# Sheet1.net
KiCad netlist of a schematic drawn in Altium Designer
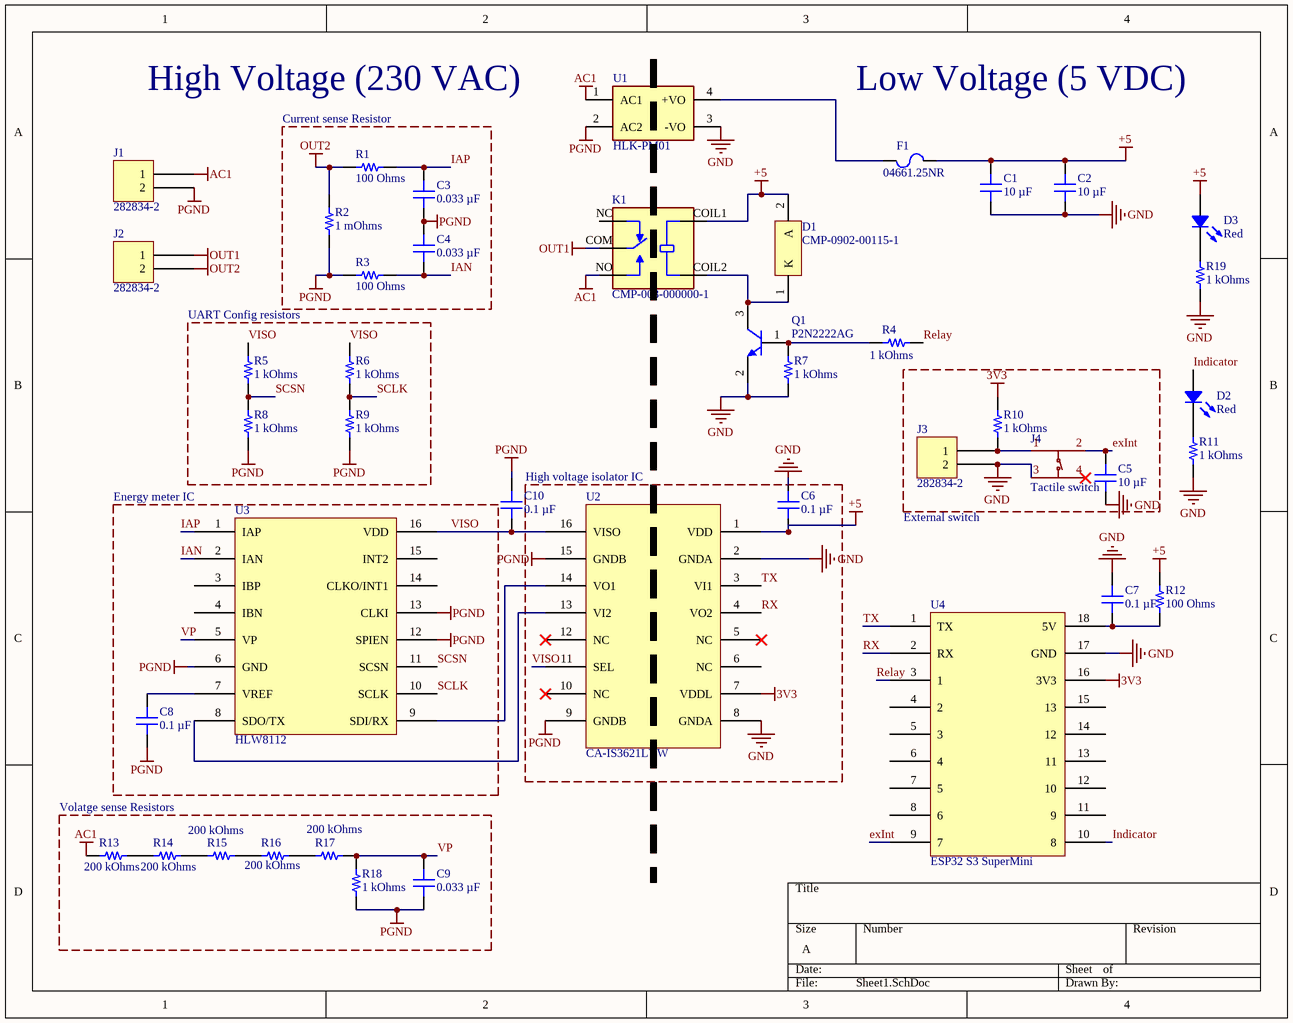
[diagram p0: Sheet1.SchDoc]

(export (version "E")
  (design (tool "Eeschema 10.0.6"))
  (components
    (comp (ref "C1")
      (value "10 µF")
      (footprint "CAP 0805_2012")
      (description "CAP CER 10UF 10V X7S 0805")
      (fields
        (field (name "PART NUMBER") "CL21Y106KPQVPNE")
        (field (name "CAPACITANCE") "10 µF")
        (field (name "MANUFACTURER") "Samsung Electro-Mechanics")
      )
      (libsource (lib "Celestial Altium Library - altium_library") (part "Capacitor"))
    )
    (comp (ref "C2")
      (value "10 µF")
      (footprint "CAP 0805_2012")
      (description "CAP CER 10UF 10V X7S 0805")
      (fields
        (field (name "PART NUMBER") "CL21Y106KPQVPNE")
        (field (name "CAPACITANCE") "10 µF")
        (field (name "MANUFACTURER") "Samsung Electro-Mechanics")
      )
      (libsource (lib "Celestial Altium Library - altium_library") (part "Capacitor"))
    )
    (comp (ref "C3")
      (value "0.033 µF")
      (footprint "CAP 0805_2012")
      (description "CAP CER 0805 33NF 50V X7R 10%")
      (fields
        (field (name "PART NUMBER") "C0805C333K5RECAUTO")
        (field (name "CAPACITANCE") "0.033 µF")
        (field (name "MANUFACTURER") "KEMET")
      )
      (libsource (lib "Celestial Altium Library - altium_library") (part "Capacitor"))
    )
    (comp (ref "C4")
      (value "0.033 µF")
      (footprint "CAP 0805_2012")
      (description "CAP CER 0805 33NF 50V X7R 10%")
      (fields
        (field (name "PART NUMBER") "C0805C333K5RECAUTO")
        (field (name "CAPACITANCE") "0.033 µF")
        (field (name "MANUFACTURER") "KEMET")
      )
      (libsource (lib "Celestial Altium Library - altium_library") (part "Capacitor"))
    )
    (comp (ref "C5")
      (value "10 µF")
      (footprint "CAP 0805_2012")
      (description "CAP CER 10UF 10V X7S 0805")
      (fields
        (field (name "PART NUMBER") "CL21Y106KPQVPNE")
        (field (name "CAPACITANCE") "10 µF")
        (field (name "MANUFACTURER") "Samsung Electro-Mechanics")
      )
      (libsource (lib "Celestial Altium Library - altium_library") (part "Capacitor"))
    )
    (comp (ref "C6")
      (value "0.1 µF")
      (footprint "CAP 0805_2012")
      (description "CAP CER 0.1UF 50V X7R 0805")
      (fields
        (field (name "PART NUMBER") "CC0805MRX7R9BB104")
        (field (name "CAPACITANCE") "0.1 µF")
        (field (name "MANUFACTURER") "Yageo")
      )
      (libsource (lib "Celestial Altium Library - altium_library") (part "Capacitor"))
    )
    (comp (ref "C7")
      (value "0.1 µF")
      (footprint "CAP 0805_2012")
      (description "CAP CER 0.1UF 50V X7R 0805")
      (fields
        (field (name "PART NUMBER") "CC0805MRX7R9BB104")
        (field (name "CAPACITANCE") "0.1 µF")
        (field (name "MANUFACTURER") "Yageo")
      )
      (libsource (lib "Celestial Altium Library - altium_library") (part "Capacitor"))
    )
    (comp (ref "C8")
      (value "0.1 µF")
      (footprint "CAP 0805_2012")
      (description "CAP CER 0.1UF 50V X7R 0805")
      (fields
        (field (name "PART NUMBER") "CC0805MRX7R9BB104")
        (field (name "CAPACITANCE") "0.1 µF")
        (field (name "MANUFACTURER") "Yageo")
      )
      (libsource (lib "Celestial Altium Library - altium_library") (part "Capacitor"))
    )
    (comp (ref "C9")
      (value "0.033 µF")
      (footprint "CAP 0805_2012")
      (description "CAP CER 0805 33NF 50V X7R 10%")
      (fields
        (field (name "PART NUMBER") "C0805C333K5RECAUTO")
        (field (name "CAPACITANCE") "0.033 µF")
        (field (name "MANUFACTURER") "KEMET")
      )
      (libsource (lib "Celestial Altium Library - altium_library") (part "Capacitor"))
    )
    (comp (ref "C10")
      (value "0.1 µF")
      (footprint "CAP 0805_2012")
      (description "CAP CER 0.1UF 50V X7R 0805")
      (fields
        (field (name "PART NUMBER") "CC0805MRX7R9BB104")
        (field (name "CAPACITANCE") "0.1 µF")
        (field (name "MANUFACTURER") "Yageo")
      )
      (libsource (lib "Celestial Altium Library - altium_library") (part "Capacitor"))
    )
    (comp (ref "D1")
      (value "CMP-0902-00115-1")
      (footprint "CMP-0902-00115-1")
      (libsource (lib "Schematic") (part "CMP-0902-00115-1"))
    )
    (comp (ref "D2")
      (value "Red")
      (footprint "LED 0805_2012 RED")
      (description "LED RED 0805 SMD")
      (fields (field (name "PART NUMBER") "5990110007F") (field (name "MANUFACTURER") "Dialight"))
      (libsource (lib "Celestial Altium Library - altium_library") (part "LED"))
    )
    (comp (ref "D3")
      (value "Red")
      (footprint "LED 0805_2012 RED")
      (description "LED RED 0805 SMD")
      (fields (field (name "PART NUMBER") "5990110007F") (field (name "MANUFACTURER") "Dialight"))
      (libsource (lib "Celestial Altium Library - altium_library") (part "LED"))
    )
    (comp (ref "F1")
      (value "04661.25NR")
      (footprint "FUSE 1206_3216 0.6MM")
      (description "FUSE BOARD MOUNT 1.25A 63VAC/VDC")
      (fields (field (name "MANUFACTURER") "Littelfuse Inc."))
      (libsource (lib "Celestial Altium Library - altium_library") (part "MOUNTED FUSE"))
    )
    (comp (ref "J1")
      (value "282834-2")
      (footprint "TE 282834-2")
      (description "TERM BLK 2P SIDE ENT 2.54MM PCB")
      (fields (field (name "MANUFACTURER") "TE Connectivity AMP Connectors") (field (name "VOLTAGE") "150V"))
      (libsource (lib "Celestial Altium Library - altium_library") (part "2 Pin"))
    )
    (comp (ref "J2")
      (value "282834-2")
      (footprint "TE 282834-2")
      (description "TERM BLK 2P SIDE ENT 2.54MM PCB")
      (fields (field (name "MANUFACTURER") "TE Connectivity AMP Connectors") (field (name "VOLTAGE") "150V"))
      (libsource (lib "Celestial Altium Library - altium_library") (part "2 Pin"))
    )
    (comp (ref "J3")
      (value "282834-2")
      (footprint "TE 282834-2")
      (description "TERM BLK 2P SIDE ENT 2.54MM PCB")
      (fields (field (name "MANUFACTURER") "TE Connectivity AMP Connectors") (field (name "VOLTAGE") "150V"))
      (libsource (lib "Celestial Altium Library - altium_library") (part "2 Pin"))
    )
    (comp (ref "J4")
      (value "Tactile switch")
      (footprint "Tactive switch")
      (libsource (lib "Integrated") (part "Tactile switch"))
    )
    (comp (ref "K1")
      (value "CMP-003-000000-1")
      (footprint "CMP-003-000000-1")
      (libsource (lib "Schematic") (part "CMP-003-000000-1"))
    )
    (comp (ref "Q1")
      (value "P2N2222AG")
      (footprint "FP-SOT23-IPC_A")
      (libsource (lib "Schematic") (part "P2N2222AG"))
    )
    (comp (ref "R1")
      (value "100 Ohms")
      (footprint "YAGEO RES 0805_2012")
      (description "RES 100 OHM 1% 1/8W 0805")
      (fields (field (name "PART NUMBER") "RC0805FR-07100RL") (field (name "MANUFACTURER") "Yageo"))
      (libsource (lib "Celestial Altium Library - altium_library") (part "Resistor"))
    )
    (comp (ref "R2")
      (value "1 mOhms")
      (footprint "RES 1206_3216")
      (description "RES 0.001 OHM 1% 1W 1206")
      (fields (field (name "PART NUMBER") "CRK0612-FZ-R001E") (field (name "MANUFACTURER") "Bourns Inc."))
      (libsource (lib "Celestial Altium Library - altium_library") (part "Resistor"))
    )
    (comp (ref "R3")
      (value "100 Ohms")
      (footprint "YAGEO RES 0805_2012")
      (description "RES 100 OHM 1% 1/8W 0805")
      (fields (field (name "PART NUMBER") "RC0805FR-07100RL") (field (name "MANUFACTURER") "Yageo"))
      (libsource (lib "Celestial Altium Library - altium_library") (part "Resistor"))
    )
    (comp (ref "R4")
      (value "1 kOhms")
      (footprint "RES 0805_2012")
      (description "RES SMD 1K OHM 0.1% 1/4W 0805")
      (fields
        (field (name "PART NUMBER") "1-2176092-8")
        (field (name "MANUFACTURER") "TE Connectivity Passive Product")
      )
      (libsource (lib "Celestial Altium Library - altium_library") (part "Resistor"))
    )
    (comp (ref "R5")
      (value "1 kOhms")
      (footprint "RES 0805_2012")
      (description "RES SMD 1K OHM 0.1% 1/4W 0805")
      (fields
        (field (name "PART NUMBER") "1-2176092-8")
        (field (name "MANUFACTURER") "TE Connectivity Passive Product")
      )
      (libsource (lib "Celestial Altium Library - altium_library") (part "Resistor"))
    )
    (comp (ref "R6")
      (value "1 kOhms")
      (footprint "RES 0805_2012")
      (description "RES SMD 1K OHM 0.1% 1/4W 0805")
      (fields
        (field (name "PART NUMBER") "1-2176092-8")
        (field (name "MANUFACTURER") "TE Connectivity Passive Product")
      )
      (libsource (lib "Celestial Altium Library - altium_library") (part "Resistor"))
    )
    (comp (ref "R7")
      (value "1 kOhms")
      (footprint "RES 0805_2012")
      (description "RES SMD 1K OHM 0.1% 1/4W 0805")
      (fields
        (field (name "PART NUMBER") "1-2176092-8")
        (field (name "MANUFACTURER") "TE Connectivity Passive Product")
      )
      (libsource (lib "Celestial Altium Library - altium_library") (part "Resistor"))
    )
    (comp (ref "R8")
      (value "1 kOhms")
      (footprint "RES 0805_2012")
      (description "RES SMD 1K OHM 0.1% 1/4W 0805")
      (fields
        (field (name "PART NUMBER") "1-2176092-8")
        (field (name "MANUFACTURER") "TE Connectivity Passive Product")
      )
      (libsource (lib "Celestial Altium Library - altium_library") (part "Resistor"))
    )
    (comp (ref "R9")
      (value "1 kOhms")
      (footprint "RES 0805_2012")
      (description "RES SMD 1K OHM 0.1% 1/4W 0805")
      (fields
        (field (name "PART NUMBER") "1-2176092-8")
        (field (name "MANUFACTURER") "TE Connectivity Passive Product")
      )
      (libsource (lib "Celestial Altium Library - altium_library") (part "Resistor"))
    )
    (comp (ref "R10")
      (value "1 kOhms")
      (footprint "RES 0805_2012")
      (description "RES SMD 1K OHM 0.1% 1/4W 0805")
      (fields
        (field (name "PART NUMBER") "1-2176092-8")
        (field (name "MANUFACTURER") "TE Connectivity Passive Product")
      )
      (libsource (lib "Celestial Altium Library - altium_library") (part "Resistor"))
    )
    (comp (ref "R11")
      (value "1 kOhms")
      (footprint "RES 0805_2012")
      (description "RES SMD 1K OHM 0.1% 1/4W 0805")
      (fields
        (field (name "PART NUMBER") "1-2176092-8")
        (field (name "MANUFACTURER") "TE Connectivity Passive Product")
      )
      (libsource (lib "Celestial Altium Library - altium_library") (part "Resistor"))
    )
    (comp (ref "R12")
      (value "100 Ohms")
      (footprint "YAGEO RES 0805_2012")
      (description "RES 100 OHM 1% 1/8W 0805")
      (fields (field (name "PART NUMBER") "RC0805FR-07100RL") (field (name "MANUFACTURER") "Yageo"))
      (libsource (lib "Celestial Altium Library - altium_library") (part "Resistor"))
    )
    (comp (ref "R13")
      (value "200 kOhms")
      (footprint "RES 2512_6432")
      (description "RES 200K OHM 1% 1W 2512")
      (fields
        (field (name "PART NUMBER") "RMCF2512FT200K")
        (field (name "MANUFACTURER") "Stackpole Electronics Inc")
      )
      (libsource (lib "Celestial Altium Library - altium_library") (part "Resistor"))
    )
    (comp (ref "R14")
      (value "200 kOhms")
      (footprint "RES 2512_6432")
      (description "RES 200K OHM 1% 1W 2512")
      (fields
        (field (name "PART NUMBER") "RMCF2512FT200K")
        (field (name "MANUFACTURER") "Stackpole Electronics Inc")
      )
      (libsource (lib "Celestial Altium Library - altium_library") (part "Resistor"))
    )
    (comp (ref "R15")
      (value "200 kOhms")
      (footprint "RES 2512_6432")
      (description "RES 200K OHM 1% 1W 2512")
      (fields
        (field (name "PART NUMBER") "RMCF2512FT200K")
        (field (name "MANUFACTURER") "Stackpole Electronics Inc")
      )
      (libsource (lib "Celestial Altium Library - altium_library") (part "Resistor"))
    )
    (comp (ref "R16")
      (value "200 kOhms")
      (footprint "RES 2512_6432")
      (description "RES 200K OHM 1% 1W 2512")
      (fields
        (field (name "PART NUMBER") "RMCF2512FT200K")
        (field (name "MANUFACTURER") "Stackpole Electronics Inc")
      )
      (libsource (lib "Celestial Altium Library - altium_library") (part "Resistor"))
    )
    (comp (ref "R17")
      (value "200 kOhms")
      (footprint "RES 2512_6432")
      (description "RES 200K OHM 1% 1W 2512")
      (fields
        (field (name "PART NUMBER") "RMCF2512FT200K")
        (field (name "MANUFACTURER") "Stackpole Electronics Inc")
      )
      (libsource (lib "Celestial Altium Library - altium_library") (part "Resistor"))
    )
    (comp (ref "R18")
      (value "1 kOhms")
      (footprint "RES 0805_2012")
      (description "RES SMD 1K OHM 0.1% 1/4W 0805")
      (fields
        (field (name "PART NUMBER") "1-2176092-8")
        (field (name "MANUFACTURER") "TE Connectivity Passive Product")
      )
      (libsource (lib "Celestial Altium Library - altium_library") (part "Resistor"))
    )
    (comp (ref "R19")
      (value "1 kOhms")
      (footprint "RES 0805_2012")
      (description "RES SMD 1K OHM 0.1% 1/4W 0805")
      (fields
        (field (name "PART NUMBER") "1-2176092-8")
        (field (name "MANUFACTURER") "TE Connectivity Passive Product")
      )
      (libsource (lib "Celestial Altium Library - altium_library") (part "Resistor"))
    )
    (comp (ref "U1")
      (value "HLK-PM01")
      (footprint "HLK-PM01")
      (libsource (lib "Schematic") (part "HLK-PM01"))
    )
    (comp (ref "U2")
      (value "CA-IS3621LVW")
      (footprint "CA-IS3621LVW")
      (libsource (lib "Integrated") (part "CA-IS3621LVW"))
    )
    (comp (ref "U3") (value "HLW8112") (footprint "HLW8112") (libsource (lib "Schematic") (part "HLW8112")))
    (comp (ref "U4")
      (value "ESP32 S3 SuperMini")
      (footprint "ESP32 S3 SuperMini")
      (libsource (lib "Schematic") (part "ESP32 S3 SuperMini"))
    )
  )
  (nets
    (net (code "1") (name "+5") (class "Default")
      (node (ref "C1") (pin "1") (pinfunction "1_1") (pintype "passive"))
      (node (ref "C2") (pin "1") (pinfunction "1_1") (pintype "passive"))
      (node (ref "C6") (pin "1") (pinfunction "1_1") (pintype "passive"))
      (node (ref "D1") (pin "2") (pinfunction "A_2") (pintype "passive"))
      (node (ref "D3") (pin "1") (pinfunction "1_1") (pintype "passive"))
      (node (ref "F1") (pin "2") (pintype "passive"))
      (node (ref "K1") (pin "COIL1") (pinfunction "COIL1_COIL1") (pintype "passive"))
      (node (ref "R12") (pin "2") (pinfunction "2_2") (pintype "passive"))
      (node (ref "U2") (pin "1") (pinfunction "VDD_1") (pintype "passive"))
    )
    (net (code "2") (name "/IAN") (class "Default")
      (node (ref "C4") (pin "1") (pinfunction "1_1") (pintype "passive"))
      (node (ref "R3") (pin "2") (pinfunction "2_2") (pintype "passive"))
      (node (ref "U3") (pin "2") (pinfunction "IAN_2") (pintype "passive"))
    )
    (net (code "3") (name "/IAP") (class "Default")
      (node (ref "C3") (pin "2") (pinfunction "2_2") (pintype "passive"))
      (node (ref "R1") (pin "2") (pinfunction "2_2") (pintype "passive"))
      (node (ref "U3") (pin "1") (pinfunction "IAP_1") (pintype "passive"))
    )
    (net (code "4") (name "/Indicator") (class "Default")
      (node (ref "D2") (pin "1") (pinfunction "1_1") (pintype "passive"))
      (node (ref "U4") (pin "10") (pinfunction "8_10") (pintype "passive"))
    )
    (net (code "5") (name "/RX") (class "Default")
      (node (ref "U2") (pin "4") (pinfunction "VO2_4") (pintype "passive"))
      (node (ref "U4") (pin "2") (pinfunction "RX_2") (pintype "passive"))
    )
    (net (code "6") (name "/Relay") (class "Default")
      (node (ref "R4") (pin "2") (pinfunction "2_2") (pintype "passive"))
      (node (ref "U4") (pin "3") (pinfunction "1_3") (pintype "passive"))
    )
    (net (code "7") (name "/SCLK") (class "Default")
      (node (ref "R6") (pin "1") (pinfunction "1_1") (pintype "passive"))
      (node (ref "R9") (pin "2") (pinfunction "2_2") (pintype "passive"))
      (node (ref "U3") (pin "10") (pinfunction "SCLK_10") (pintype "passive"))
    )
    (net (code "8") (name "/SCSN") (class "Default")
      (node (ref "R5") (pin "1") (pinfunction "1_1") (pintype "passive"))
      (node (ref "R8") (pin "2") (pinfunction "2_2") (pintype "passive"))
      (node (ref "U3") (pin "11") (pinfunction "SCSN_11") (pintype "passive"))
    )
    (net (code "9") (name "/TX") (class "Default")
      (node (ref "U2") (pin "3") (pinfunction "VI1_3") (pintype "passive"))
      (node (ref "U4") (pin "1") (pinfunction "TX_1") (pintype "passive"))
    )
    (net (code "10") (name "/VISO") (class "Default")
      (node (ref "C10") (pin "1") (pinfunction "1_1") (pintype "passive"))
      (node (ref "R5") (pin "2") (pinfunction "2_2") (pintype "passive"))
      (node (ref "R6") (pin "2") (pinfunction "2_2") (pintype "passive"))
      (node (ref "U2") (pin "11") (pinfunction "SEL_11") (pintype "passive"))
      (node (ref "U2") (pin "16") (pinfunction "VISO_16") (pintype "passive"))
      (node (ref "U3") (pin "16") (pinfunction "VDD_16") (pintype "passive"))
    )
    (net (code "11") (name "/VP") (class "Default")
      (node (ref "C9") (pin "2") (pinfunction "2_2") (pintype "passive"))
      (node (ref "R17") (pin "2") (pinfunction "2_2") (pintype "passive"))
      (node (ref "R18") (pin "2") (pinfunction "2_2") (pintype "passive"))
      (node (ref "U3") (pin "5") (pinfunction "VP_5") (pintype "passive"))
    )
    (net (code "12") (name "/exInt") (class "Default")
      (node (ref "C5") (pin "1") (pinfunction "1_1") (pintype "passive"))
      (node (ref "J4") (pin "2") (pinfunction "B_2") (pintype "passive"))
      (node (ref "U4") (pin "9") (pinfunction "7_9") (pintype "passive"))
    )
    (net (code "13") (name "3V3") (class "Default")
      (node (ref "R10") (pin "1") (pinfunction "1_1") (pintype "passive"))
      (node (ref "U2") (pin "7") (pinfunction "VDDL_7") (pintype "passive"))
      (node (ref "U4") (pin "16") (pinfunction "3V3_16") (pintype "passive"))
    )
    (net (code "14") (name "AC1") (class "Default")
      (node (ref "J1") (pin "1") (pinfunction "1_1") (pintype "passive"))
      (node (ref "K1") (pin "NO") (pinfunction "NO_NO") (pintype "passive"))
      (node (ref "R13") (pin "1") (pinfunction "1_1") (pintype "passive"))
      (node (ref "U1") (pin "1") (pinfunction "AC1_1") (pintype "passive"))
    )
    (net (code "15") (name "GND") (class "Default")
      (node (ref "C1") (pin "2") (pinfunction "2_2") (pintype "passive"))
      (node (ref "C2") (pin "2") (pinfunction "2_2") (pintype "passive"))
      (node (ref "C5") (pin "2") (pinfunction "2_2") (pintype "passive"))
      (node (ref "C6") (pin "2") (pinfunction "2_2") (pintype "passive"))
      (node (ref "C7") (pin "2") (pinfunction "2_2") (pintype "passive"))
      (node (ref "J3") (pin "2") (pinfunction "2_2") (pintype "passive"))
      (node (ref "J4") (pin "3") (pinfunction "C_3") (pintype "passive"))
      (node (ref "Q1") (pin "2") (pinfunction "E_2") (pintype "passive"))
      (node (ref "R11") (pin "2") (pinfunction "2_2") (pintype "passive"))
      (node (ref "R19") (pin "2") (pinfunction "2_2") (pintype "passive"))
      (node (ref "R7") (pin "1") (pinfunction "1_1") (pintype "passive"))
      (node (ref "U1") (pin "3") (pinfunction "-VO_3") (pintype "passive"))
      (node (ref "U2") (pin "2") (pinfunction "GNDA_2") (pintype "passive"))
      (node (ref "U2") (pin "8") (pinfunction "GNDA_8") (pintype "passive"))
      (node (ref "U4") (pin "17") (pinfunction "GND_17") (pintype "passive"))
    )
    (net (code "16") (name "Net-(D1-K)") (class "Default")
      (node (ref "D1") (pin "1") (pinfunction "K_1") (pintype "passive"))
      (node (ref "K1") (pin "COIL2") (pinfunction "COIL2_COIL2") (pintype "passive"))
      (node (ref "Q1") (pin "3") (pinfunction "C_3") (pintype "passive"))
    )
    (net (code "17") (name "Net-(D2-Pad2)") (class "Default")
      (node (ref "D2") (pin "2") (pinfunction "2_2") (pintype "passive"))
      (node (ref "R11") (pin "1") (pinfunction "1_1") (pintype "passive"))
    )
    (net (code "18") (name "Net-(D3-Pad2)") (class "Default")
      (node (ref "D3") (pin "2") (pinfunction "2_2") (pintype "passive"))
      (node (ref "R19") (pin "1") (pinfunction "1_1") (pintype "passive"))
    )
    (net (code "19") (name "Net-(J4-A)") (class "Default")
      (node (ref "J3") (pin "1") (pinfunction "1_1") (pintype "passive"))
      (node (ref "J4") (pin "1") (pinfunction "A_1") (pintype "passive"))
      (node (ref "R10") (pin "2") (pinfunction "2_2") (pintype "passive"))
    )
    (net (code "20") (name "Net-(Q1-B)") (class "Default")
      (node (ref "Q1") (pin "1") (pinfunction "B_1") (pintype "passive"))
      (node (ref "R4") (pin "1") (pinfunction "1_1") (pintype "passive"))
      (node (ref "R7") (pin "2") (pinfunction "2_2") (pintype "passive"))
    )
    (net (code "21") (name "Net-(R13-Pad2)") (class "Default")
      (node (ref "R13") (pin "2") (pinfunction "2_2") (pintype "passive"))
      (node (ref "R14") (pin "1") (pinfunction "1_1") (pintype "passive"))
    )
    (net (code "22") (name "Net-(R14-Pad2)") (class "Default")
      (node (ref "R14") (pin "2") (pinfunction "2_2") (pintype "passive"))
      (node (ref "R15") (pin "1") (pinfunction "1_1") (pintype "passive"))
    )
    (net (code "23") (name "Net-(R15-Pad2)") (class "Default")
      (node (ref "R15") (pin "2") (pinfunction "2_2") (pintype "passive"))
      (node (ref "R16") (pin "1") (pinfunction "1_1") (pintype "passive"))
    )
    (net (code "24") (name "Net-(R16-Pad2)") (class "Default")
      (node (ref "R16") (pin "2") (pinfunction "2_2") (pintype "passive"))
      (node (ref "R17") (pin "1") (pinfunction "1_1") (pintype "passive"))
    )
    (net (code "25") (name "Net-(U1-+VO)") (class "Default")
      (node (ref "F1") (pin "1") (pintype "passive"))
      (node (ref "U1") (pin "4") (pinfunction "+VO_4") (pintype "passive"))
    )
    (net (code "26") (name "Net-(U2-VI2)") (class "Default")
      (node (ref "U2") (pin "13") (pinfunction "VI2_13") (pintype "passive"))
      (node (ref "U3") (pin "8") (pinfunction "SDO/TX_8") (pintype "passive"))
    )
    (net (code "27") (name "Net-(U2-VO1)") (class "Default")
      (node (ref "U2") (pin "14") (pinfunction "VO1_14") (pintype "passive"))
      (node (ref "U3") (pin "9") (pinfunction "SDI/RX_9") (pintype "passive"))
    )
    (net (code "28") (name "Net-(U3-VREF)") (class "Default")
      (node (ref "C8") (pin "2") (pinfunction "2_2") (pintype "passive"))
      (node (ref "U3") (pin "7") (pinfunction "VREF_7") (pintype "passive"))
    )
    (net (code "29") (name "Net-(U4-5V)") (class "Default")
      (node (ref "C7") (pin "1") (pinfunction "1_1") (pintype "passive"))
      (node (ref "R12") (pin "1") (pinfunction "1_1") (pintype "passive"))
      (node (ref "U4") (pin "18") (pinfunction "5V_18") (pintype "passive"))
    )
    (net (code "30") (name "OUT1") (class "Default")
      (node (ref "J2") (pin "1") (pinfunction "1_1") (pintype "passive"))
      (node (ref "K1") (pin "COM") (pinfunction "COM_COM") (pintype "passive"))
    )
    (net (code "31") (name "OUT2") (class "Default")
      (node (ref "J2") (pin "2") (pinfunction "2_2") (pintype "passive"))
      (node (ref "R1") (pin "1") (pinfunction "1_1") (pintype "passive"))
      (node (ref "R2") (pin "2") (pinfunction "2_2") (pintype "passive"))
    )
    (net (code "32") (name "PGND") (class "Default")
      (node (ref "C10") (pin "2") (pinfunction "2_2") (pintype "passive"))
      (node (ref "C3") (pin "1") (pinfunction "1_1") (pintype "passive"))
      (node (ref "C4") (pin "2") (pinfunction "2_2") (pintype "passive"))
      (node (ref "C8") (pin "1") (pinfunction "1_1") (pintype "passive"))
      (node (ref "C9") (pin "1") (pinfunction "1_1") (pintype "passive"))
      (node (ref "J1") (pin "2") (pinfunction "2_2") (pintype "passive"))
      (node (ref "R18") (pin "1") (pinfunction "1_1") (pintype "passive"))
      (node (ref "R2") (pin "1") (pinfunction "1_1") (pintype "passive"))
      (node (ref "R3") (pin "1") (pinfunction "1_1") (pintype "passive"))
      (node (ref "R8") (pin "1") (pinfunction "1_1") (pintype "passive"))
      (node (ref "R9") (pin "1") (pinfunction "1_1") (pintype "passive"))
      (node (ref "U1") (pin "2") (pinfunction "AC2_2") (pintype "passive"))
      (node (ref "U2") (pin "15") (pinfunction "GNDB_15") (pintype "passive"))
      (node (ref "U2") (pin "9") (pinfunction "GNDB_9") (pintype "passive"))
      (node (ref "U3") (pin "12") (pinfunction "SPIEN_12") (pintype "passive"))
      (node (ref "U3") (pin "13") (pinfunction "CLKI_13") (pintype "passive"))
      (node (ref "U3") (pin "6") (pinfunction "GND_6") (pintype "passive"))
    )
    (net (code "33") (name "unconnected-(J4-D-Pad4)") (class "Default")
      (node (ref "J4") (pin "4") (pinfunction "D_4") (pintype "passive+no_connect"))
    )
    (net (code "34") (name "unconnected-(K1-PadNC)") (class "Default")
      (node (ref "K1") (pin "NC") (pinfunction "NC_NC") (pintype "passive"))
    )
    (net (code "35") (name "unconnected-(U2-NC-Pad5)") (class "Default")
      (node (ref "U2") (pin "5") (pinfunction "NC_5") (pintype "passive+no_connect"))
    )
    (net (code "36") (name "unconnected-(U2-NC-Pad6)") (class "Default")
      (node (ref "U2") (pin "6") (pinfunction "NC_6") (pintype "passive"))
    )
    (net (code "37") (name "unconnected-(U2-NC-Pad10)") (class "Default")
      (node (ref "U2") (pin "10") (pinfunction "NC_10") (pintype "passive+no_connect"))
    )
    (net (code "38") (name "unconnected-(U2-NC-Pad12)") (class "Default")
      (node (ref "U2") (pin "12") (pinfunction "NC_12") (pintype "passive+no_connect"))
    )
    (net (code "39") (name "unconnected-(U3-CLKO{slash}INT1-Pad14)") (class "Default")
      (node (ref "U3") (pin "14") (pinfunction "CLKO/INT1_14") (pintype "passive"))
    )
    (net (code "40") (name "unconnected-(U3-IBN-Pad4)") (class "Default")
      (node (ref "U3") (pin "4") (pinfunction "IBN_4") (pintype "passive"))
    )
    (net (code "41") (name "unconnected-(U3-IBP-Pad3)") (class "Default")
      (node (ref "U3") (pin "3") (pinfunction "IBP_3") (pintype "passive"))
    )
    (net (code "42") (name "unconnected-(U3-INT2-Pad15)") (class "Default")
      (node (ref "U3") (pin "15") (pinfunction "INT2_15") (pintype "passive"))
    )
    (net (code "43") (name "unconnected-(U4-2-Pad4)") (class "Default")
      (node (ref "U4") (pin "4") (pinfunction "2_4") (pintype "passive"))
    )
    (net (code "44") (name "unconnected-(U4-3-Pad5)") (class "Default")
      (node (ref "U4") (pin "5") (pinfunction "3_5") (pintype "passive"))
    )
    (net (code "45") (name "unconnected-(U4-4-Pad6)") (class "Default")
      (node (ref "U4") (pin "6") (pinfunction "4_6") (pintype "passive"))
    )
    (net (code "46") (name "unconnected-(U4-5-Pad7)") (class "Default")
      (node (ref "U4") (pin "7") (pinfunction "5_7") (pintype "passive"))
    )
    (net (code "47") (name "unconnected-(U4-6-Pad8)") (class "Default")
      (node (ref "U4") (pin "8") (pinfunction "6_8") (pintype "passive"))
    )
    (net (code "48") (name "unconnected-(U4-9-Pad11)") (class "Default")
      (node (ref "U4") (pin "11") (pinfunction "9_11") (pintype "passive"))
    )
    (net (code "49") (name "unconnected-(U4-10-Pad12)") (class "Default")
      (node (ref "U4") (pin "12") (pinfunction "10_12") (pintype "passive"))
    )
    (net (code "50") (name "unconnected-(U4-11-Pad13)") (class "Default")
      (node (ref "U4") (pin "13") (pinfunction "11_13") (pintype "passive"))
    )
    (net (code "51") (name "unconnected-(U4-12-Pad14)") (class "Default")
      (node (ref "U4") (pin "14") (pinfunction "12_14") (pintype "passive"))
    )
    (net (code "52") (name "unconnected-(U4-13-Pad15)") (class "Default")
      (node (ref "U4") (pin "15") (pinfunction "13_15") (pintype "passive"))
    )
  )
)
